# SchematicDesign.net
KiCad netlist of a schematic drawn in EAGLE
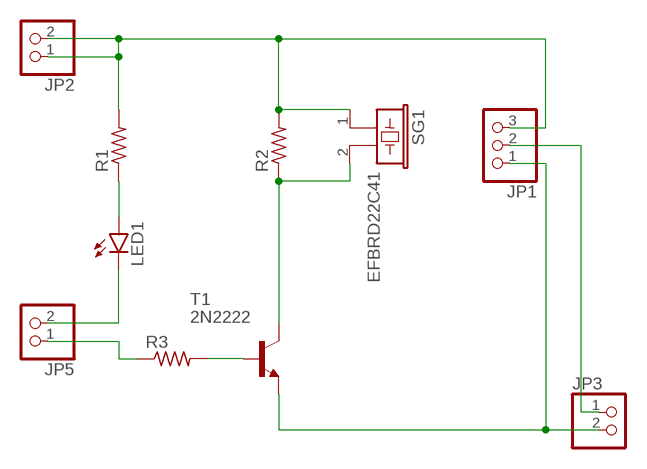
[diagram p0: schematic, sheet 1]

(export (version "E")
  (design (tool "Eeschema 10.0.6"))
  (components
    (comp (ref "JP1")
      (value "PINHD-1X3")
      (footprint "eagle-import:1X03")
      (libsource (lib "eagle-import") (part "PINHD-1X3"))
    )
    (comp (ref "JP2")
      (value "PINHD-1X2")
      (footprint "eagle-import:1X02")
      (libsource (lib "eagle-import") (part "PINHD-1X2"))
    )
    (comp (ref "JP3")
      (value "PINHD-1X2")
      (footprint "eagle-import:1X02")
      (libsource (lib "eagle-import") (part "PINHD-1X2"))
    )
    (comp (ref "JP5")
      (value "PINHD-1X2")
      (footprint "eagle-import:1X02")
      (libsource (lib "eagle-import") (part "PINHD-1X2"))
    )
    (comp (ref "LED1")
      (value "LED5MM")
      (footprint "eagle-import:LED5MM")
      (libsource (lib "eagle-import") (part "LED5MM"))
    )
    (comp (ref "R1")
      (value "R-US_0207/10")
      (footprint "eagle-import:0207_10")
      (libsource (lib "eagle-import") (part "R-US_0207/10"))
    )
    (comp (ref "R2")
      (value "R-US_0207/10")
      (footprint "eagle-import:0207_10")
      (libsource (lib "eagle-import") (part "R-US_0207/10"))
    )
    (comp (ref "R3")
      (value "R-US_0207/10")
      (footprint "eagle-import:0207_10")
      (libsource (lib "eagle-import") (part "R-US_0207/10"))
    )
    (comp (ref "SG1")
      (value "EFBRD22C41")
      (footprint "eagle-import:EFBRD22C41")
      (libsource (lib "eagle-import") (part "EFB?RD22C41"))
    )
    (comp (ref "T1")
      (value "2N2222")
      (footprint "eagle-import:TO18")
      (libsource (lib "eagle-import") (part "2N2222"))
    )
  )
  (nets
    (net (code "1") (name "Net-(JP1-Pad2)") (class "Default")
      (node (ref "JP1") (pin "2") (pinfunction "2_2") (pintype "passive"))
      (node (ref "JP3") (pin "1") (pinfunction "1_1") (pintype "passive"))
    )
    (net (code "2") (name "Net-(JP1-Pad3)") (class "Default")
      (node (ref "JP1") (pin "3") (pinfunction "3_3") (pintype "passive"))
      (node (ref "JP2") (pin "1") (pinfunction "1_1") (pintype "passive"))
      (node (ref "JP2") (pin "2") (pinfunction "2_2") (pintype "passive"))
      (node (ref "R1") (pin "2") (pinfunction "2_2") (pintype "passive"))
      (node (ref "R2") (pin "2") (pinfunction "2_2") (pintype "passive"))
      (node (ref "SG1") (pin "1") (pinfunction "1_1") (pintype "passive"))
    )
    (net (code "3") (name "Net-(JP5-Pad1)") (class "Default")
      (node (ref "JP5") (pin "1") (pinfunction "1_1") (pintype "passive"))
      (node (ref "R3") (pin "1") (pinfunction "1_1") (pintype "passive"))
    )
    (net (code "4") (name "Net-(LED1-C)") (class "Default")
      (node (ref "JP5") (pin "2") (pinfunction "2_2") (pintype "passive"))
      (node (ref "LED1") (pin "K") (pinfunction "C_K") (pintype "passive"))
    )
    (net (code "5") (name "Net-(LED1-PadA)") (class "Default")
      (node (ref "LED1") (pin "A") (pinfunction "A_A") (pintype "passive"))
      (node (ref "R1") (pin "1") (pinfunction "1_1") (pintype "passive"))
    )
    (net (code "6") (name "Net-(T1-B)") (class "Default")
      (node (ref "R3") (pin "2") (pinfunction "2_2") (pintype "passive"))
      (node (ref "T1") (pin "2") (pinfunction "B_2") (pintype "passive"))
    )
    (net (code "7") (name "Net-(T1-C)") (class "Default")
      (node (ref "R2") (pin "1") (pinfunction "1_1") (pintype "passive"))
      (node (ref "SG1") (pin "2") (pinfunction "2_2") (pintype "passive"))
      (node (ref "T1") (pin "3") (pinfunction "C_3") (pintype "passive"))
    )
    (net (code "8") (name "Net-(T1-E)") (class "Default")
      (node (ref "JP1") (pin "1") (pinfunction "1_1") (pintype "passive"))
      (node (ref "JP3") (pin "2") (pinfunction "2_2") (pintype "passive"))
      (node (ref "T1") (pin "1") (pinfunction "E_1") (pintype "passive"))
    )
  )
)
